# NEMOTIC_HORSE.net
KiCad netlist of a schematic drawn in EAGLE
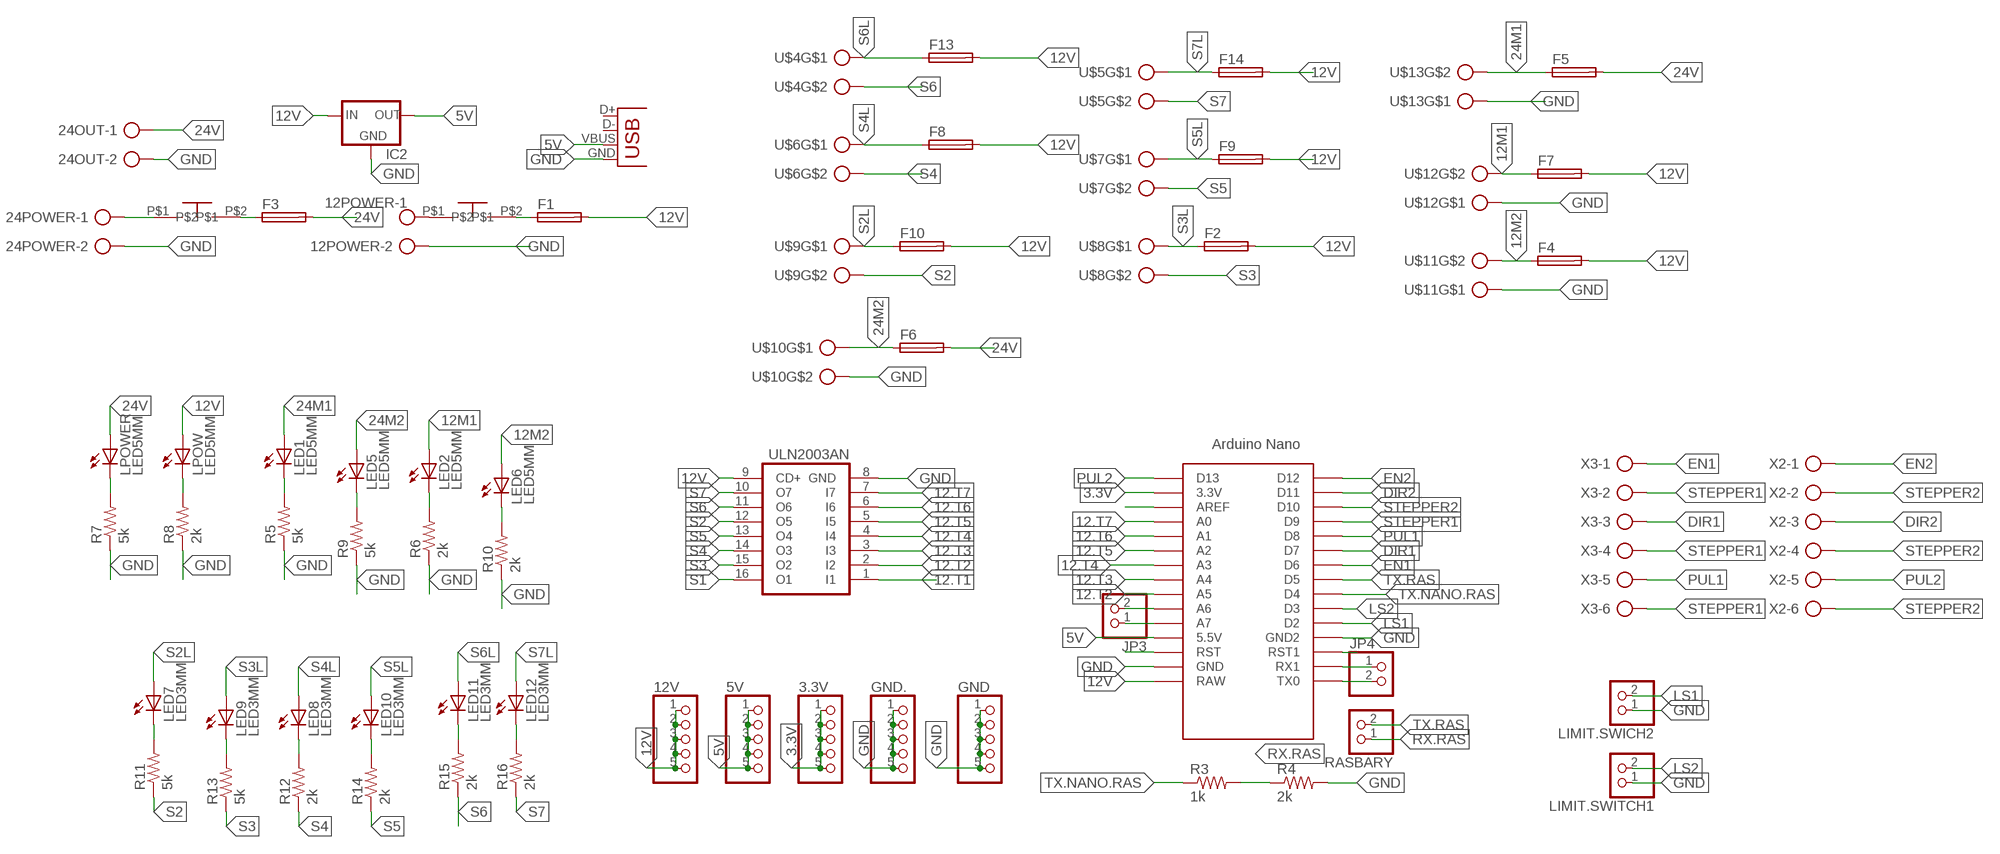
[diagram p0: schematic, sheet 1]

(export (version "E")
  (design (tool "Eeschema 10.0.6"))
  (components
    (comp (ref "3.3V")
      (value "PINHD-1X5")
      (footprint "eagle-import:1X05")
      (libsource (lib "eagle-import") (part "PINHD-1X5"))
    )
    (comp (ref "5V")
      (value "PINHD-1X5")
      (footprint "eagle-import:1X05")
      (libsource (lib "eagle-import") (part "PINHD-1X5"))
    )
    (comp (ref "12POWER")
      (value "ROSTA.POWER")
      (footprint "eagle-import:W239-302")
      (libsource (lib "eagle-import") (part "ROSTA.POWER"))
    )
    (comp (ref "12V")
      (value "PINHD-1X5")
      (footprint "eagle-import:1X05")
      (libsource (lib "eagle-import") (part "PINHD-1X5"))
    )
    (comp (ref "24OUT")
      (value "ROSTA.POWER")
      (footprint "eagle-import:W239-302")
      (libsource (lib "eagle-import") (part "ROSTA.POWER"))
    )
    (comp (ref "24POWER")
      (value "ROSTA.POWER")
      (footprint "eagle-import:W239-302")
      (libsource (lib "eagle-import") (part "ROSTA.POWER"))
    )
    (comp (ref "F1")
      (value "FUSE_HOLDER")
      (footprint "eagle-import:SH22,5A")
      (libsource (lib "eagle-import") (part "FUSE_HOLDER"))
    )
    (comp (ref "F2")
      (value "FUSE_HOLDER")
      (footprint "eagle-import:SH22,5A")
      (libsource (lib "eagle-import") (part "FUSE_HOLDER"))
    )
    (comp (ref "F3")
      (value "FUSE_HOLDER")
      (footprint "eagle-import:SH22,5A")
      (libsource (lib "eagle-import") (part "FUSE_HOLDER"))
    )
    (comp (ref "F4")
      (value "FUSE_HOLDER")
      (footprint "eagle-import:SH22,5A")
      (libsource (lib "eagle-import") (part "FUSE_HOLDER"))
    )
    (comp (ref "F5")
      (value "FUSE_HOLDER")
      (footprint "eagle-import:SH22,5A")
      (libsource (lib "eagle-import") (part "FUSE_HOLDER"))
    )
    (comp (ref "F6")
      (value "FUSE_HOLDER")
      (footprint "eagle-import:SH22,5A")
      (libsource (lib "eagle-import") (part "FUSE_HOLDER"))
    )
    (comp (ref "F7")
      (value "FUSE_HOLDER")
      (footprint "eagle-import:SH22,5A")
      (libsource (lib "eagle-import") (part "FUSE_HOLDER"))
    )
    (comp (ref "F8")
      (value "FUSE_HOLDER")
      (footprint "eagle-import:SH22,5A")
      (libsource (lib "eagle-import") (part "FUSE_HOLDER"))
    )
    (comp (ref "F9")
      (value "FUSE_HOLDER")
      (footprint "eagle-import:SH22,5A")
      (libsource (lib "eagle-import") (part "FUSE_HOLDER"))
    )
    (comp (ref "F10")
      (value "FUSE_HOLDER")
      (footprint "eagle-import:SH22,5A")
      (libsource (lib "eagle-import") (part "FUSE_HOLDER"))
    )
    (comp (ref "F13")
      (value "FUSE_HOLDER")
      (footprint "eagle-import:SH22,5A")
      (libsource (lib "eagle-import") (part "FUSE_HOLDER"))
    )
    (comp (ref "F14")
      (value "FUSE_HOLDER")
      (footprint "eagle-import:SH22,5A")
      (libsource (lib "eagle-import") (part "FUSE_HOLDER"))
    )
    (comp (ref "GND")
      (value "PINHD-1X5")
      (footprint "eagle-import:1X05")
      (libsource (lib "eagle-import") (part "PINHD-1X5"))
    )
    (comp (ref "GND.")
      (value "PINHD-1X5")
      (footprint "eagle-import:1X05")
      (libsource (lib "eagle-import") (part "PINHD-1X5"))
    )
    (comp (ref "IC1")
      (value "ULN2003AN")
      (footprint "eagle-import:DIL16")
      (libsource (lib "eagle-import") (part "ULN2003AN"))
    )
    (comp (ref "IC2")
      (value "78XXS")
      (footprint "eagle-import:78XXS")
      (libsource (lib "eagle-import") (part "78XXS"))
    )
    (comp (ref "JP3")
      (value "PINHD-1X2")
      (footprint "eagle-import:1X02")
      (libsource (lib "eagle-import") (part "PINHD-1X2"))
    )
    (comp (ref "JP4")
      (value "PINHD-1X2")
      (footprint "eagle-import:1X02")
      (libsource (lib "eagle-import") (part "PINHD-1X2"))
    )
    (comp (ref "LED1")
      (value "LED5MM")
      (footprint "eagle-import:LED5MM")
      (libsource (lib "eagle-import") (part "LED5MM"))
    )
    (comp (ref "LED2")
      (value "LED5MM")
      (footprint "eagle-import:LED5MM")
      (libsource (lib "eagle-import") (part "LED5MM"))
    )
    (comp (ref "LED5")
      (value "LED5MM")
      (footprint "eagle-import:LED5MM")
      (libsource (lib "eagle-import") (part "LED5MM"))
    )
    (comp (ref "LED6")
      (value "LED5MM")
      (footprint "eagle-import:LED5MM")
      (libsource (lib "eagle-import") (part "LED5MM"))
    )
    (comp (ref "LED7")
      (value "LED3MM")
      (footprint "eagle-import:LED3MM")
      (libsource (lib "eagle-import") (part "LED3MM"))
    )
    (comp (ref "LED8")
      (value "LED3MM")
      (footprint "eagle-import:LED3MM")
      (libsource (lib "eagle-import") (part "LED3MM"))
    )
    (comp (ref "LED9")
      (value "LED3MM")
      (footprint "eagle-import:LED3MM")
      (libsource (lib "eagle-import") (part "LED3MM"))
    )
    (comp (ref "LED10")
      (value "LED3MM")
      (footprint "eagle-import:LED3MM")
      (libsource (lib "eagle-import") (part "LED3MM"))
    )
    (comp (ref "LED11")
      (value "LED3MM")
      (footprint "eagle-import:LED3MM")
      (libsource (lib "eagle-import") (part "LED3MM"))
    )
    (comp (ref "LED12")
      (value "LED3MM")
      (footprint "eagle-import:LED3MM")
      (libsource (lib "eagle-import") (part "LED3MM"))
    )
    (comp (ref "LIMIT.SWICH2")
      (value "PINHD-1X2")
      (footprint "eagle-import:1X02")
      (libsource (lib "eagle-import") (part "PINHD-1X2"))
    )
    (comp (ref "LIMIT.SWITCH1")
      (value "PINHD-1X2")
      (footprint "eagle-import:1X02")
      (libsource (lib "eagle-import") (part "PINHD-1X2"))
    )
    (comp (ref "LPOW")
      (value "LED5MM")
      (footprint "eagle-import:LED5MM")
      (libsource (lib "eagle-import") (part "LED5MM"))
    )
    (comp (ref "LPOWER")
      (value "LED5MM")
      (footprint "eagle-import:LED5MM")
      (libsource (lib "eagle-import") (part "LED5MM"))
    )
    (comp (ref "R3")
      (value "1k")
      (footprint "eagle-import:0204_7")
      (libsource (lib "eagle-import") (part "RES-7"))
    )
    (comp (ref "R4")
      (value "2k")
      (footprint "eagle-import:0204_7")
      (libsource (lib "eagle-import") (part "RES-7"))
    )
    (comp (ref "R5")
      (value "5k")
      (footprint "eagle-import:0204_7")
      (libsource (lib "eagle-import") (part "RES-7"))
    )
    (comp (ref "R6")
      (value "2k")
      (footprint "eagle-import:0204_7")
      (libsource (lib "eagle-import") (part "RES-7"))
    )
    (comp (ref "R7")
      (value "5k")
      (footprint "eagle-import:0204_7")
      (libsource (lib "eagle-import") (part "R-US_0204/7"))
    )
    (comp (ref "R8")
      (value "2k")
      (footprint "eagle-import:0204_7")
      (libsource (lib "eagle-import") (part "RES-7"))
    )
    (comp (ref "R9")
      (value "5k")
      (footprint "eagle-import:0204_7")
      (libsource (lib "eagle-import") (part "RES-7"))
    )
    (comp (ref "R10")
      (value "2k")
      (footprint "eagle-import:0204_7")
      (libsource (lib "eagle-import") (part "RES-7"))
    )
    (comp (ref "R11")
      (value "5k")
      (footprint "eagle-import:0204_5")
      (libsource (lib "eagle-import") (part "RES-5"))
    )
    (comp (ref "R12")
      (value "2k")
      (footprint "eagle-import:0204_5")
      (libsource (lib "eagle-import") (part "RES-5"))
    )
    (comp (ref "R13")
      (value "5k")
      (footprint "eagle-import:0204_5")
      (libsource (lib "eagle-import") (part "RES-5"))
    )
    (comp (ref "R14")
      (value "2k")
      (footprint "eagle-import:0204_5")
      (libsource (lib "eagle-import") (part "RES-5"))
    )
    (comp (ref "R15")
      (value "2k")
      (footprint "eagle-import:0204_5")
      (libsource (lib "eagle-import") (part "RES-5"))
    )
    (comp (ref "R16")
      (value "2k")
      (footprint "eagle-import:0204_5")
      (libsource (lib "eagle-import") (part "RES-5"))
    )
    (comp (ref "RASBARY")
      (value "PINHD-1X2")
      (footprint "eagle-import:1X02")
      (libsource (lib "eagle-import") (part "PINHD-1X2"))
    )
    (comp (ref "RASBERY.POWER")
      (value "USB-A-H")
      (footprint "eagle-import:USB-A-H")
      (libsource (lib "eagle-import") (part "USB-A-H"))
    )
    (comp (ref "U$1")
      (value "ARDUINO_NANO")
      (footprint "eagle-import:NANO")
      (libsource (lib "eagle-import") (part "ARDUINO_NANO"))
    )
    (comp (ref "U$2")
      (value "SWITCH_2")
      (footprint "eagle-import:ON_OFF")
      (libsource (lib "eagle-import") (part "SWITCH_2"))
    )
    (comp (ref "U$3")
      (value "SWITCH_2")
      (footprint "eagle-import:ON_OFF")
      (libsource (lib "eagle-import") (part "SWITCH_2"))
    )
    (comp (ref "U$4")
      (value "CON_PTR_2")
      (footprint "eagle-import:AK300_2")
      (libsource (lib "eagle-import") (part "CON_PTR_2"))
    )
    (comp (ref "U$5")
      (value "CON_PTR_2")
      (footprint "eagle-import:AK300_2")
      (libsource (lib "eagle-import") (part "CON_PTR_2"))
    )
    (comp (ref "U$6")
      (value "CON_PTR_2")
      (footprint "eagle-import:AK300_2")
      (libsource (lib "eagle-import") (part "CON_PTR_2"))
    )
    (comp (ref "U$7")
      (value "CON_PTR_2")
      (footprint "eagle-import:AK300_2")
      (libsource (lib "eagle-import") (part "CON_PTR_2"))
    )
    (comp (ref "U$8")
      (value "CON_PTR_2")
      (footprint "eagle-import:AK300_2")
      (libsource (lib "eagle-import") (part "CON_PTR_2"))
    )
    (comp (ref "U$9")
      (value "CON_PTR_2")
      (footprint "eagle-import:AK300_2")
      (libsource (lib "eagle-import") (part "CON_PTR_2"))
    )
    (comp (ref "U$10")
      (value "CON_PTR_2")
      (footprint "eagle-import:AK300_2")
      (libsource (lib "eagle-import") (part "CON_PTR_2"))
    )
    (comp (ref "U$11")
      (value "CON_PTR_2")
      (footprint "eagle-import:AK300_2")
      (libsource (lib "eagle-import") (part "CON_PTR_2"))
    )
    (comp (ref "U$12")
      (value "CON_PTR_2")
      (footprint "eagle-import:AK300_2")
      (libsource (lib "eagle-import") (part "CON_PTR_2"))
    )
    (comp (ref "U$13")
      (value "CON_PTR_2")
      (footprint "eagle-import:AK300_2")
      (libsource (lib "eagle-import") (part "CON_PTR_2"))
    )
    (comp (ref "X2")
      (value "CON_PTR_6")
      (footprint "eagle-import:AK300_6")
      (fields (field (name "SPICEPREFIX") "X"))
      (libsource (lib "eagle-import") (part "CON_PTR_6"))
    )
    (comp (ref "X3")
      (value "CON_PTR_6")
      (footprint "eagle-import:AK300_6")
      (fields (field (name "SPICEPREFIX") "X"))
      (libsource (lib "eagle-import") (part "CON_PTR_6"))
    )
  )
  (nets
    (net (code "1") (name "3.3V") (class "Default")
      (node (ref "3.3V") (pin "1") (pinfunction "1_1") (pintype "passive"))
      (node (ref "3.3V") (pin "2") (pinfunction "2_2") (pintype "passive"))
      (node (ref "3.3V") (pin "3") (pinfunction "3_3") (pintype "passive"))
      (node (ref "3.3V") (pin "4") (pinfunction "4_4") (pintype "passive"))
      (node (ref "3.3V") (pin "5") (pinfunction "5_5") (pintype "passive"))
      (node (ref "U$1") (pin "3.3V") (pinfunction "3.3V_3.3V") (pintype "bidirectional"))
    )
    (net (code "2") (name "5V") (class "Default")
      (node (ref "5V") (pin "1") (pinfunction "1_1") (pintype "passive"))
      (node (ref "5V") (pin "2") (pinfunction "2_2") (pintype "passive"))
      (node (ref "5V") (pin "3") (pinfunction "3_3") (pintype "passive"))
      (node (ref "5V") (pin "4") (pinfunction "4_4") (pintype "passive"))
      (node (ref "5V") (pin "5") (pinfunction "5_5") (pintype "passive"))
      (node (ref "IC2") (pin "OUT") (pinfunction "OUT_OUT") (pintype "passive"))
      (node (ref "RASBERY.POWER") (pin "VBUS") (pinfunction "VBUS_VBUS") (pintype "bidirectional"))
      (node (ref "U$1") (pin "5V") (pinfunction "5.5V_5V") (pintype "bidirectional"))
    )
    (net (code "3") (name "12.T1") (class "Default")
      (node (ref "IC1") (pin "1") (pinfunction "I1_1") (pintype "input"))
    )
    (net (code "4") (name "12.T2") (class "Default")
      (node (ref "IC1") (pin "2") (pinfunction "I2_2") (pintype "input"))
      (node (ref "U$1") (pin "A5") (pinfunction "A5_A5") (pintype "bidirectional"))
    )
    (net (code "5") (name "12.T3") (class "Default")
      (node (ref "IC1") (pin "3") (pinfunction "I3_3") (pintype "input"))
      (node (ref "U$1") (pin "A4") (pinfunction "A4_A4") (pintype "bidirectional"))
    )
    (net (code "6") (name "12.T4") (class "Default")
      (node (ref "IC1") (pin "4") (pinfunction "I4_4") (pintype "input"))
      (node (ref "U$1") (pin "A3") (pinfunction "A3_A3") (pintype "bidirectional"))
    )
    (net (code "7") (name "12.T5") (class "Default")
      (node (ref "IC1") (pin "5") (pinfunction "I5_5") (pintype "input"))
      (node (ref "U$1") (pin "A2") (pinfunction "A2_A2") (pintype "bidirectional"))
    )
    (net (code "8") (name "12.T6") (class "Default")
      (node (ref "IC1") (pin "6") (pinfunction "I6_6") (pintype "input"))
      (node (ref "U$1") (pin "A1") (pinfunction "A1_A1") (pintype "bidirectional"))
    )
    (net (code "9") (name "12.T7") (class "Default")
      (node (ref "IC1") (pin "7") (pinfunction "I7_7") (pintype "input"))
      (node (ref "U$1") (pin "A0") (pinfunction "A0_A0") (pintype "bidirectional"))
    )
    (net (code "10") (name "12M1") (class "Default")
      (node (ref "F7") (pin "1") (pinfunction "1_1") (pintype "passive"))
      (node (ref "LED2") (pin "A") (pinfunction "A_A") (pintype "passive"))
      (node (ref "U$12") (pin "2") (pinfunction "KL_2") (pintype "passive"))
    )
    (net (code "11") (name "12M2") (class "Default")
      (node (ref "F4") (pin "1") (pinfunction "1_1") (pintype "passive"))
      (node (ref "LED6") (pin "A") (pinfunction "A_A") (pintype "passive"))
      (node (ref "U$11") (pin "2") (pinfunction "KL_2") (pintype "passive"))
    )
    (net (code "12") (name "12V") (class "Default")
      (node (ref "12V") (pin "1") (pinfunction "1_1") (pintype "passive"))
      (node (ref "12V") (pin "2") (pinfunction "2_2") (pintype "passive"))
      (node (ref "12V") (pin "3") (pinfunction "3_3") (pintype "passive"))
      (node (ref "12V") (pin "4") (pinfunction "4_4") (pintype "passive"))
      (node (ref "12V") (pin "5") (pinfunction "5_5") (pintype "passive"))
      (node (ref "F1") (pin "2") (pinfunction "2_2") (pintype "passive"))
      (node (ref "F10") (pin "2") (pinfunction "2_2") (pintype "passive"))
      (node (ref "F13") (pin "2") (pinfunction "2_2") (pintype "passive"))
      (node (ref "F14") (pin "2") (pinfunction "2_2") (pintype "passive"))
      (node (ref "F2") (pin "2") (pinfunction "2_2") (pintype "passive"))
      (node (ref "F4") (pin "2") (pinfunction "2_2") (pintype "passive"))
      (node (ref "F7") (pin "2") (pinfunction "2_2") (pintype "passive"))
      (node (ref "F8") (pin "2") (pinfunction "2_2") (pintype "passive"))
      (node (ref "F9") (pin "2") (pinfunction "2_2") (pintype "passive"))
      (node (ref "IC1") (pin "9") (pinfunction "CD+_9") (pintype "passive"))
      (node (ref "IC2") (pin "IN") (pinfunction "IN_IN") (pintype "input"))
      (node (ref "LPOW") (pin "A") (pinfunction "A_A") (pintype "passive"))
      (node (ref "U$1") (pin "RAW") (pinfunction "RAW_RAW") (pintype "bidirectional"))
    )
    (net (code "13") (name "24M1") (class "Default")
      (node (ref "F5") (pin "1") (pinfunction "1_1") (pintype "passive"))
      (node (ref "LED1") (pin "A") (pinfunction "A_A") (pintype "passive"))
      (node (ref "U$13") (pin "2") (pinfunction "KL_2") (pintype "passive"))
    )
    (net (code "14") (name "24M2") (class "Default")
      (node (ref "F6") (pin "1") (pinfunction "1_1") (pintype "passive"))
      (node (ref "LED5") (pin "A") (pinfunction "A_A") (pintype "passive"))
      (node (ref "U$10") (pin "1") (pinfunction "KL_1") (pintype "passive"))
    )
    (net (code "15") (name "24V") (class "Default")
      (node (ref "24OUT") (pin "1") (pinfunction "KL_1") (pintype "passive"))
      (node (ref "F3") (pin "2") (pinfunction "2_2") (pintype "passive"))
      (node (ref "F5") (pin "2") (pinfunction "2_2") (pintype "passive"))
      (node (ref "F6") (pin "2") (pinfunction "2_2") (pintype "passive"))
      (node (ref "LPOWER") (pin "A") (pinfunction "A_A") (pintype "passive"))
    )
    (net (code "16") (name "DIR1") (class "Default")
      (node (ref "U$1") (pin "D7") (pinfunction "D7_D7") (pintype "bidirectional"))
      (node (ref "X3") (pin "3") (pinfunction "KL_3") (pintype "passive"))
    )
    (net (code "17") (name "DIR2") (class "Default")
      (node (ref "U$1") (pin "D11") (pinfunction "D11_D11") (pintype "bidirectional"))
      (node (ref "X2") (pin "3") (pinfunction "KL_3") (pintype "passive"))
    )
    (net (code "18") (name "EN1") (class "Default")
      (node (ref "U$1") (pin "D6") (pinfunction "D6_D6") (pintype "bidirectional"))
      (node (ref "X3") (pin "1") (pinfunction "KL_1") (pintype "passive"))
    )
    (net (code "19") (name "EN2") (class "Default")
      (node (ref "U$1") (pin "D12") (pinfunction "D12_D12") (pintype "bidirectional"))
      (node (ref "X2") (pin "1") (pinfunction "KL_1") (pintype "passive"))
    )
    (net (code "20") (name "GND") (class "Default")
      (node (ref "12POWER") (pin "2") (pinfunction "KL_2") (pintype "passive"))
      (node (ref "24OUT") (pin "2") (pinfunction "KL_2") (pintype "passive"))
      (node (ref "24POWER") (pin "2") (pinfunction "KL_2") (pintype "passive"))
      (node (ref "GND") (pin "1") (pinfunction "1_1") (pintype "passive"))
      (node (ref "GND") (pin "2") (pinfunction "2_2") (pintype "passive"))
      (node (ref "GND") (pin "3") (pinfunction "3_3") (pintype "passive"))
      (node (ref "GND") (pin "4") (pinfunction "4_4") (pintype "passive"))
      (node (ref "GND") (pin "5") (pinfunction "5_5") (pintype "passive"))
      (node (ref "GND.") (pin "1") (pinfunction "1_1") (pintype "passive"))
      (node (ref "GND.") (pin "2") (pinfunction "2_2") (pintype "passive"))
      (node (ref "GND.") (pin "3") (pinfunction "3_3") (pintype "passive"))
      (node (ref "GND.") (pin "4") (pinfunction "4_4") (pintype "passive"))
      (node (ref "GND.") (pin "5") (pinfunction "5_5") (pintype "passive"))
      (node (ref "IC1") (pin "8") (pinfunction "GND_8") (pintype "power_in"))
      (node (ref "IC2") (pin "GND") (pinfunction "GND_GND") (pintype "input"))
      (node (ref "LIMIT.SWICH2") (pin "1") (pinfunction "1_1") (pintype "passive"))
      (node (ref "LIMIT.SWITCH1") (pin "1") (pinfunction "1_1") (pintype "passive"))
      (node (ref "R10") (pin "1") (pinfunction "1_1") (pintype "passive"))
      (node (ref "R4") (pin "2") (pinfunction "2_2") (pintype "passive"))
      (node (ref "R5") (pin "1") (pinfunction "1_1") (pintype "passive"))
      (node (ref "R6") (pin "1") (pinfunction "1_1") (pintype "passive"))
      (node (ref "R7") (pin "1") (pinfunction "1_1") (pintype "passive"))
      (node (ref "R8") (pin "1") (pinfunction "1_1") (pintype "passive"))
      (node (ref "R9") (pin "1") (pinfunction "1_1") (pintype "passive"))
      (node (ref "RASBERY.POWER") (pin "GND") (pinfunction "GND_GND") (pintype "bidirectional"))
      (node (ref "U$1") (pin "GND") (pinfunction "GND_GND") (pintype "bidirectional"))
      (node (ref "U$1") (pin "GND1") (pinfunction "GND2_GND1") (pintype "bidirectional"))
      (node (ref "U$10") (pin "2") (pinfunction "KL_2") (pintype "passive"))
      (node (ref "U$11") (pin "1") (pinfunction "KL_1") (pintype "passive"))
      (node (ref "U$12") (pin "1") (pinfunction "KL_1") (pintype "passive"))
      (node (ref "U$13") (pin "1") (pinfunction "KL_1") (pintype "passive"))
    )
    (net (code "21") (name "LS1") (class "Default")
      (node (ref "LIMIT.SWICH2") (pin "2") (pinfunction "2_2") (pintype "passive"))
      (node (ref "U$1") (pin "D2") (pinfunction "D2_D2") (pintype "bidirectional"))
    )
    (net (code "22") (name "LS2") (class "Default")
      (node (ref "LIMIT.SWITCH1") (pin "2") (pinfunction "2_2") (pintype "passive"))
      (node (ref "U$1") (pin "D3") (pinfunction "D3_D3") (pintype "bidirectional"))
    )
    (net (code "23") (name "Net-(12POWERA-KL)") (class "Default")
      (node (ref "12POWER") (pin "1") (pinfunction "KL_1") (pintype "passive"))
      (node (ref "U$3") (pin "P$1") (pinfunction "P$1_P$1") (pintype "bidirectional"))
    )
    (net (code "24") (name "Net-(24POWERA-KL)") (class "Default")
      (node (ref "24POWER") (pin "1") (pinfunction "KL_1") (pintype "passive"))
      (node (ref "U$2") (pin "P$1") (pinfunction "P$1_P$1") (pintype "bidirectional"))
    )
    (net (code "25") (name "Net-(F1-Pad1)") (class "Default")
      (node (ref "F1") (pin "1") (pinfunction "1_1") (pintype "passive"))
      (node (ref "U$3") (pin "P$2") (pinfunction "P$2_P$2") (pintype "bidirectional"))
    )
    (net (code "26") (name "Net-(F3-Pad1)") (class "Default")
      (node (ref "F3") (pin "1") (pinfunction "1_1") (pintype "passive"))
      (node (ref "U$2") (pin "P$2") (pinfunction "P$2_P$2") (pintype "bidirectional"))
    )
    (net (code "27") (name "Net-(JP3-Pad1)") (class "Default")
      (node (ref "JP3") (pin "1") (pinfunction "1_1") (pintype "passive"))
      (node (ref "U$1") (pin "A7") (pinfunction "A7_A7") (pintype "bidirectional"))
    )
    (net (code "28") (name "Net-(JP3-Pad2)") (class "Default")
      (node (ref "JP3") (pin "2") (pinfunction "2_2") (pintype "passive"))
      (node (ref "U$1") (pin "A6") (pinfunction "A6_A6") (pintype "bidirectional"))
    )
    (net (code "29") (name "Net-(JP4-Pad1)") (class "Default")
      (node (ref "JP4") (pin "1") (pinfunction "1_1") (pintype "passive"))
      (node (ref "U$1") (pin "RX1") (pinfunction "RX1_RX1") (pintype "bidirectional"))
    )
    (net (code "30") (name "Net-(JP4-Pad2)") (class "Default")
      (node (ref "JP4") (pin "2") (pinfunction "2_2") (pintype "passive"))
      (node (ref "U$1") (pin "TX0") (pinfunction "TX0_TX0") (pintype "bidirectional"))
    )
    (net (code "31") (name "Net-(LED1-C)") (class "Default")
      (node (ref "LED1") (pin "K") (pinfunction "C_K") (pintype "passive"))
      (node (ref "R5") (pin "2") (pinfunction "2_2") (pintype "passive"))
    )
    (net (code "32") (name "Net-(LED2-C)") (class "Default")
      (node (ref "LED2") (pin "K") (pinfunction "C_K") (pintype "passive"))
      (node (ref "R6") (pin "2") (pinfunction "2_2") (pintype "passive"))
    )
    (net (code "33") (name "Net-(LED5-C)") (class "Default")
      (node (ref "LED5") (pin "K") (pinfunction "C_K") (pintype "passive"))
      (node (ref "R9") (pin "2") (pinfunction "2_2") (pintype "passive"))
    )
    (net (code "34") (name "Net-(LED6-C)") (class "Default")
      (node (ref "LED6") (pin "K") (pinfunction "C_K") (pintype "passive"))
      (node (ref "R10") (pin "2") (pinfunction "2_2") (pintype "passive"))
    )
    (net (code "35") (name "Net-(LED7-C)") (class "Default")
      (node (ref "LED7") (pin "K") (pinfunction "C_K") (pintype "passive"))
      (node (ref "R11") (pin "2") (pinfunction "2_2") (pintype "passive"))
    )
    (net (code "36") (name "Net-(LED8-C)") (class "Default")
      (node (ref "LED8") (pin "K") (pinfunction "C_K") (pintype "passive"))
      (node (ref "R12") (pin "2") (pinfunction "2_2") (pintype "passive"))
    )
    (net (code "37") (name "Net-(LED9-C)") (class "Default")
      (node (ref "LED9") (pin "K") (pinfunction "C_K") (pintype "passive"))
      (node (ref "R13") (pin "2") (pinfunction "2_2") (pintype "passive"))
    )
    (net (code "38") (name "Net-(LED10-C)") (class "Default")
      (node (ref "LED10") (pin "K") (pinfunction "C_K") (pintype "passive"))
      (node (ref "R14") (pin "2") (pinfunction "2_2") (pintype "passive"))
    )
    (net (code "39") (name "Net-(LED11-C)") (class "Default")
      (node (ref "LED11") (pin "K") (pinfunction "C_K") (pintype "passive"))
      (node (ref "R15") (pin "2") (pinfunction "2_2") (pintype "passive"))
    )
    (net (code "40") (name "Net-(LED12-C)") (class "Default")
      (node (ref "LED12") (pin "K") (pinfunction "C_K") (pintype "passive"))
      (node (ref "R16") (pin "2") (pinfunction "2_2") (pintype "passive"))
    )
    (net (code "41") (name "Net-(LPOW-C)") (class "Default")
      (node (ref "LPOW") (pin "K") (pinfunction "C_K") (pintype "passive"))
      (node (ref "R8") (pin "2") (pinfunction "2_2") (pintype "passive"))
    )
    (net (code "42") (name "Net-(LPOWER-C)") (class "Default")
      (node (ref "LPOWER") (pin "K") (pinfunction "C_K") (pintype "passive"))
      (node (ref "R7") (pin "2") (pinfunction "2_2") (pintype "passive"))
    )
    (net (code "43") (name "PUL1") (class "Default")
      (node (ref "U$1") (pin "D8") (pinfunction "D8_D8") (pintype "bidirectional"))
      (node (ref "X3") (pin "5") (pinfunction "KL_5") (pintype "passive"))
    )
    (net (code "44") (name "PUL2") (class "Default")
      (node (ref "U$1") (pin "D13") (pinfunction "D13_D13") (pintype "bidirectional"))
      (node (ref "X2") (pin "5") (pinfunction "KL_5") (pintype "passive"))
    )
    (net (code "45") (name "RX.RAS") (class "Default")
      (node (ref "R3") (pin "2") (pinfunction "2_2") (pintype "passive"))
      (node (ref "R4") (pin "1") (pinfunction "1_1") (pintype "passive"))
      (node (ref "RASBARY") (pin "1") (pinfunction "1_1") (pintype "passive"))
    )
    (net (code "46") (name "S1") (class "Default")
      (node (ref "IC1") (pin "16") (pinfunction "O1_16") (pintype "open_collector"))
    )
    (net (code "47") (name "S2") (class "Default")
      (node (ref "IC1") (pin "12") (pinfunction "O5_12") (pintype "open_collector"))
      (node (ref "R11") (pin "1") (pinfunction "1_1") (pintype "passive"))
      (node (ref "U$9") (pin "2") (pinfunction "KL_2") (pintype "passive"))
    )
    (net (code "48") (name "S2L") (class "Default")
      (node (ref "F10") (pin "1") (pinfunction "1_1") (pintype "passive"))
      (node (ref "LED7") (pin "A") (pinfunction "A_A") (pintype "passive"))
      (node (ref "U$9") (pin "1") (pinfunction "KL_1") (pintype "passive"))
    )
    (net (code "49") (name "S3") (class "Default")
      (node (ref "IC1") (pin "15") (pinfunction "O2_15") (pintype "open_collector"))
      (node (ref "R13") (pin "1") (pinfunction "1_1") (pintype "passive"))
      (node (ref "U$8") (pin "2") (pinfunction "KL_2") (pintype "passive"))
    )
    (net (code "50") (name "S3L") (class "Default")
      (node (ref "F2") (pin "1") (pinfunction "1_1") (pintype "passive"))
      (node (ref "LED9") (pin "A") (pinfunction "A_A") (pintype "passive"))
      (node (ref "U$8") (pin "1") (pinfunction "KL_1") (pintype "passive"))
    )
    (net (code "51") (name "S4") (class "Default")
      (node (ref "IC1") (pin "14") (pinfunction "O3_14") (pintype "open_collector"))
      (node (ref "R12") (pin "1") (pinfunction "1_1") (pintype "passive"))
      (node (ref "U$6") (pin "2") (pinfunction "KL_2") (pintype "passive"))
    )
    (net (code "52") (name "S4L") (class "Default")
      (node (ref "F8") (pin "1") (pinfunction "1_1") (pintype "passive"))
      (node (ref "LED8") (pin "A") (pinfunction "A_A") (pintype "passive"))
      (node (ref "U$6") (pin "1") (pinfunction "KL_1") (pintype "passive"))
    )
    (net (code "53") (name "S5") (class "Default")
      (node (ref "IC1") (pin "13") (pinfunction "O4_13") (pintype "open_collector"))
      (node (ref "R14") (pin "1") (pinfunction "1_1") (pintype "passive"))
      (node (ref "U$7") (pin "2") (pinfunction "KL_2") (pintype "passive"))
    )
    (net (code "54") (name "S5L") (class "Default")
      (node (ref "F9") (pin "1") (pinfunction "1_1") (pintype "passive"))
      (node (ref "LED10") (pin "A") (pinfunction "A_A") (pintype "passive"))
      (node (ref "U$7") (pin "1") (pinfunction "KL_1") (pintype "passive"))
    )
    (net (code "55") (name "S6") (class "Default")
      (node (ref "IC1") (pin "11") (pinfunction "O6_11") (pintype "open_collector"))
      (node (ref "R15") (pin "1") (pinfunction "1_1") (pintype "passive"))
      (node (ref "U$4") (pin "2") (pinfunction "KL_2") (pintype "passive"))
    )
    (net (code "56") (name "S6L") (class "Default")
      (node (ref "F13") (pin "1") (pinfunction "1_1") (pintype "passive"))
      (node (ref "LED11") (pin "A") (pinfunction "A_A") (pintype "passive"))
      (node (ref "U$4") (pin "1") (pinfunction "KL_1") (pintype "passive"))
    )
    (net (code "57") (name "S7") (class "Default")
      (node (ref "IC1") (pin "10") (pinfunction "O7_10") (pintype "open_collector"))
      (node (ref "R16") (pin "1") (pinfunction "1_1") (pintype "passive"))
      (node (ref "U$5") (pin "2") (pinfunction "KL_2") (pintype "passive"))
    )
    (net (code "58") (name "S7L") (class "Default")
      (node (ref "F14") (pin "1") (pinfunction "1_1") (pintype "passive"))
      (node (ref "LED12") (pin "A") (pinfunction "A_A") (pintype "passive"))
      (node (ref "U$5") (pin "1") (pinfunction "KL_1") (pintype "passive"))
    )
    (net (code "59") (name "STEPPER1") (class "Default")
      (node (ref "U$1") (pin "D9") (pinfunction "D9_D9") (pintype "bidirectional"))
      (node (ref "X3") (pin "2") (pinfunction "KL_2") (pintype "passive"))
      (node (ref "X3") (pin "4") (pinfunction "KL_4") (pintype "passive"))
      (node (ref "X3") (pin "6") (pinfunction "KL_6") (pintype "passive"))
    )
    (net (code "60") (name "STEPPER2") (class "Default")
      (node (ref "U$1") (pin "D10") (pinfunction "D10_D10") (pintype "bidirectional"))
      (node (ref "X2") (pin "2") (pinfunction "KL_2") (pintype "passive"))
      (node (ref "X2") (pin "4") (pinfunction "KL_4") (pintype "passive"))
      (node (ref "X2") (pin "6") (pinfunction "KL_6") (pintype "passive"))
    )
    (net (code "61") (name "TX.NANO.RAS") (class "Default")
      (node (ref "R3") (pin "1") (pinfunction "1_1") (pintype "passive"))
      (node (ref "U$1") (pin "D4") (pinfunction "D4_D4") (pintype "bidirectional"))
    )
    (net (code "62") (name "TX.RAS") (class "Default")
      (node (ref "RASBARY") (pin "2") (pinfunction "2_2") (pintype "passive"))
      (node (ref "U$1") (pin "D5") (pinfunction "D5_D5") (pintype "bidirectional"))
    )
    (net (code "63") (name "unconnected-(RASBERY.POWER-PadD+)") (class "Default")
      (node (ref "RASBERY.POWER") (pin "D+") (pinfunction "D+_D+") (pintype "bidirectional"))
    )
    (net (code "64") (name "unconnected-(RASBERY.POWER-PadD-)") (class "Default")
      (node (ref "RASBERY.POWER") (pin "D-") (pinfunction "D-_D-") (pintype "bidirectional"))
    )
    (net (code "65") (name "unconnected-(U$1-PadAREF)") (class "Default")
      (node (ref "U$1") (pin "AREF") (pinfunction "AREF_AREF") (pintype "bidirectional"))
    )
    (net (code "66") (name "unconnected-(U$1-PadRST)") (class "Default")
      (node (ref "U$1") (pin "RST") (pinfunction "RST_RST") (pintype "bidirectional"))
    )
    (net (code "67") (name "unconnected-(U$1-PadRST1)") (class "Default")
      (node (ref "U$1") (pin "RST1") (pinfunction "RST1_RST1") (pintype "bidirectional"))
    )
  )
)
